# USBCONN_MICROAB_BM.net
KiCad netlist of a schematic drawn in Altium Designer
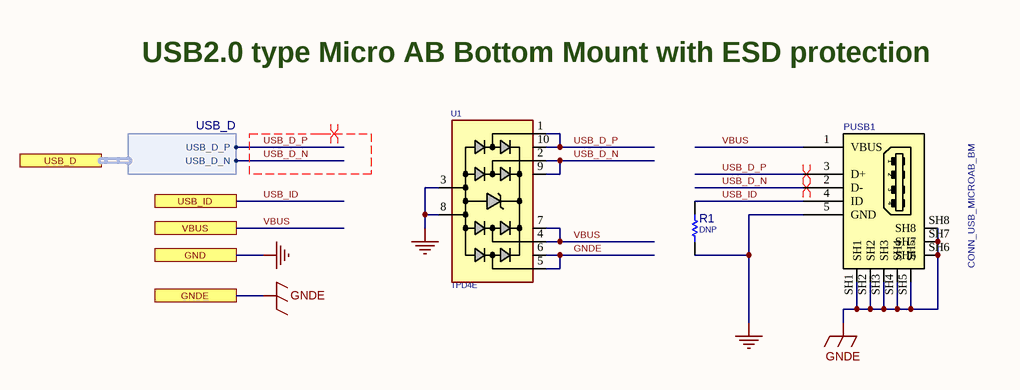
[diagram p0: USBCONN_MICROAB_BM.SchDoc]

(export (version "E")
  (design (tool "Eeschema 10.0.6"))
  (components
    (comp (ref "PUSB1")
      (value "CONN_USB_MICROAB_BM")
      (footprint "USB_MICRO_AB_BM_SHT")
      (description "CONN, USB, MICRO AB, R/A, SMD, BOTTOM MOUNT")
      (fields (field (name "MANF_P#") "47589-0001") (field (name "MANF") "MOLEX"))
      (libsource (lib "conn_usb") (part "CONN_USB_MICRO_AB_BM_SHT"))
    )
    (comp (ref "R1")
      (value "DNP")
      (footprint "R0402")
      (description "RESISTOR, SMD")
      (libsource (lib "res_smd_passive") (part "RES_SMD"))
    )
    (comp (ref "U1")
      (value "TPD4E")
      (footprint "SON50_10_2510")
      (description "TVS, ESD PROTECT, 4CH,")
      (fields (field (name "MANF_P#") "TPD4E05U06DQA") (field (name "MANF") "Texas Instruments"))
      (libsource (lib "protect_tvs_esd_fuse") (part "TVS_X4_TPD4E05U06"))
    )
  )
  (nets
    (net (code "2") (name "/USB_D_N") (class "Default")
      (node (ref "PUSB1") (pin "2") (pinfunction "D-_2") (pintype "passive"))
      (node (ref "U1") (pin "2") (pinfunction "2_2") (pintype "passive"))
      (node (ref "U1") (pin "9") (pinfunction "9_9") (pintype "passive"))
    )
    (net (code "3") (name "/USB_D_P") (class "Default")
      (node (ref "PUSB1") (pin "3") (pinfunction "D+_3") (pintype "passive"))
      (node (ref "U1") (pin "1") (pinfunction "1_1") (pintype "passive"))
      (node (ref "U1") (pin "10") (pinfunction "10_10") (pintype "passive"))
    )
    (net (code "4") (name "/USB_ID") (class "Default")
      (node (ref "PUSB1") (pin "4") (pinfunction "ID_4") (pintype "power_in"))
      (node (ref "R1") (pin "2") (pinfunction "2_2") (pintype "passive"))
    )
    (net (code "5") (name "/VBUS") (class "Default")
      (node (ref "PUSB1") (pin "1") (pinfunction "VBUS_1") (pintype "power_in"))
      (node (ref "U1") (pin "4") (pinfunction "4_4") (pintype "passive"))
      (node (ref "U1") (pin "7") (pinfunction "7_7") (pintype "passive"))
    )
    (net (code "7") (name "GND") (class "Default")
      (node (ref "PUSB1") (pin "5") (pinfunction "GND_5") (pintype "power_in"))
      (node (ref "R1") (pin "1") (pinfunction "1_1") (pintype "passive"))
      (node (ref "U1") (pin "3") (pinfunction "3_3") (pintype "passive"))
      (node (ref "U1") (pin "8") (pinfunction "8_8") (pintype "passive"))
    )
    (net (code "8") (name "GNDE") (class "Default")
      (node (ref "PUSB1") (pin "SH1") (pinfunction "SH1_SH1") (pintype "passive"))
      (node (ref "PUSB1") (pin "SH2") (pinfunction "SH2_SH2") (pintype "passive"))
      (node (ref "PUSB1") (pin "SH3") (pinfunction "SH3_SH3") (pintype "passive"))
      (node (ref "PUSB1") (pin "SH4") (pinfunction "SH4_SH4") (pintype "passive"))
      (node (ref "PUSB1") (pin "SH5") (pinfunction "SH5_SH5") (pintype "passive"))
      (node (ref "PUSB1") (pin "SH6") (pinfunction "SH6_SH6") (pintype "passive"))
      (node (ref "PUSB1") (pin "SH7") (pinfunction "SH7_SH7") (pintype "passive"))
      (node (ref "PUSB1") (pin "SH8") (pinfunction "SH8_SH8") (pintype "passive"))
      (node (ref "U1") (pin "5") (pinfunction "5_5") (pintype "passive"))
      (node (ref "U1") (pin "6") (pinfunction "6_6") (pintype "passive"))
    )
  )
)
